# Pyr0-Piezo_Direct_Extruder_Board2_0_0.net
KiCad netlist of a schematic drawn in EAGLE
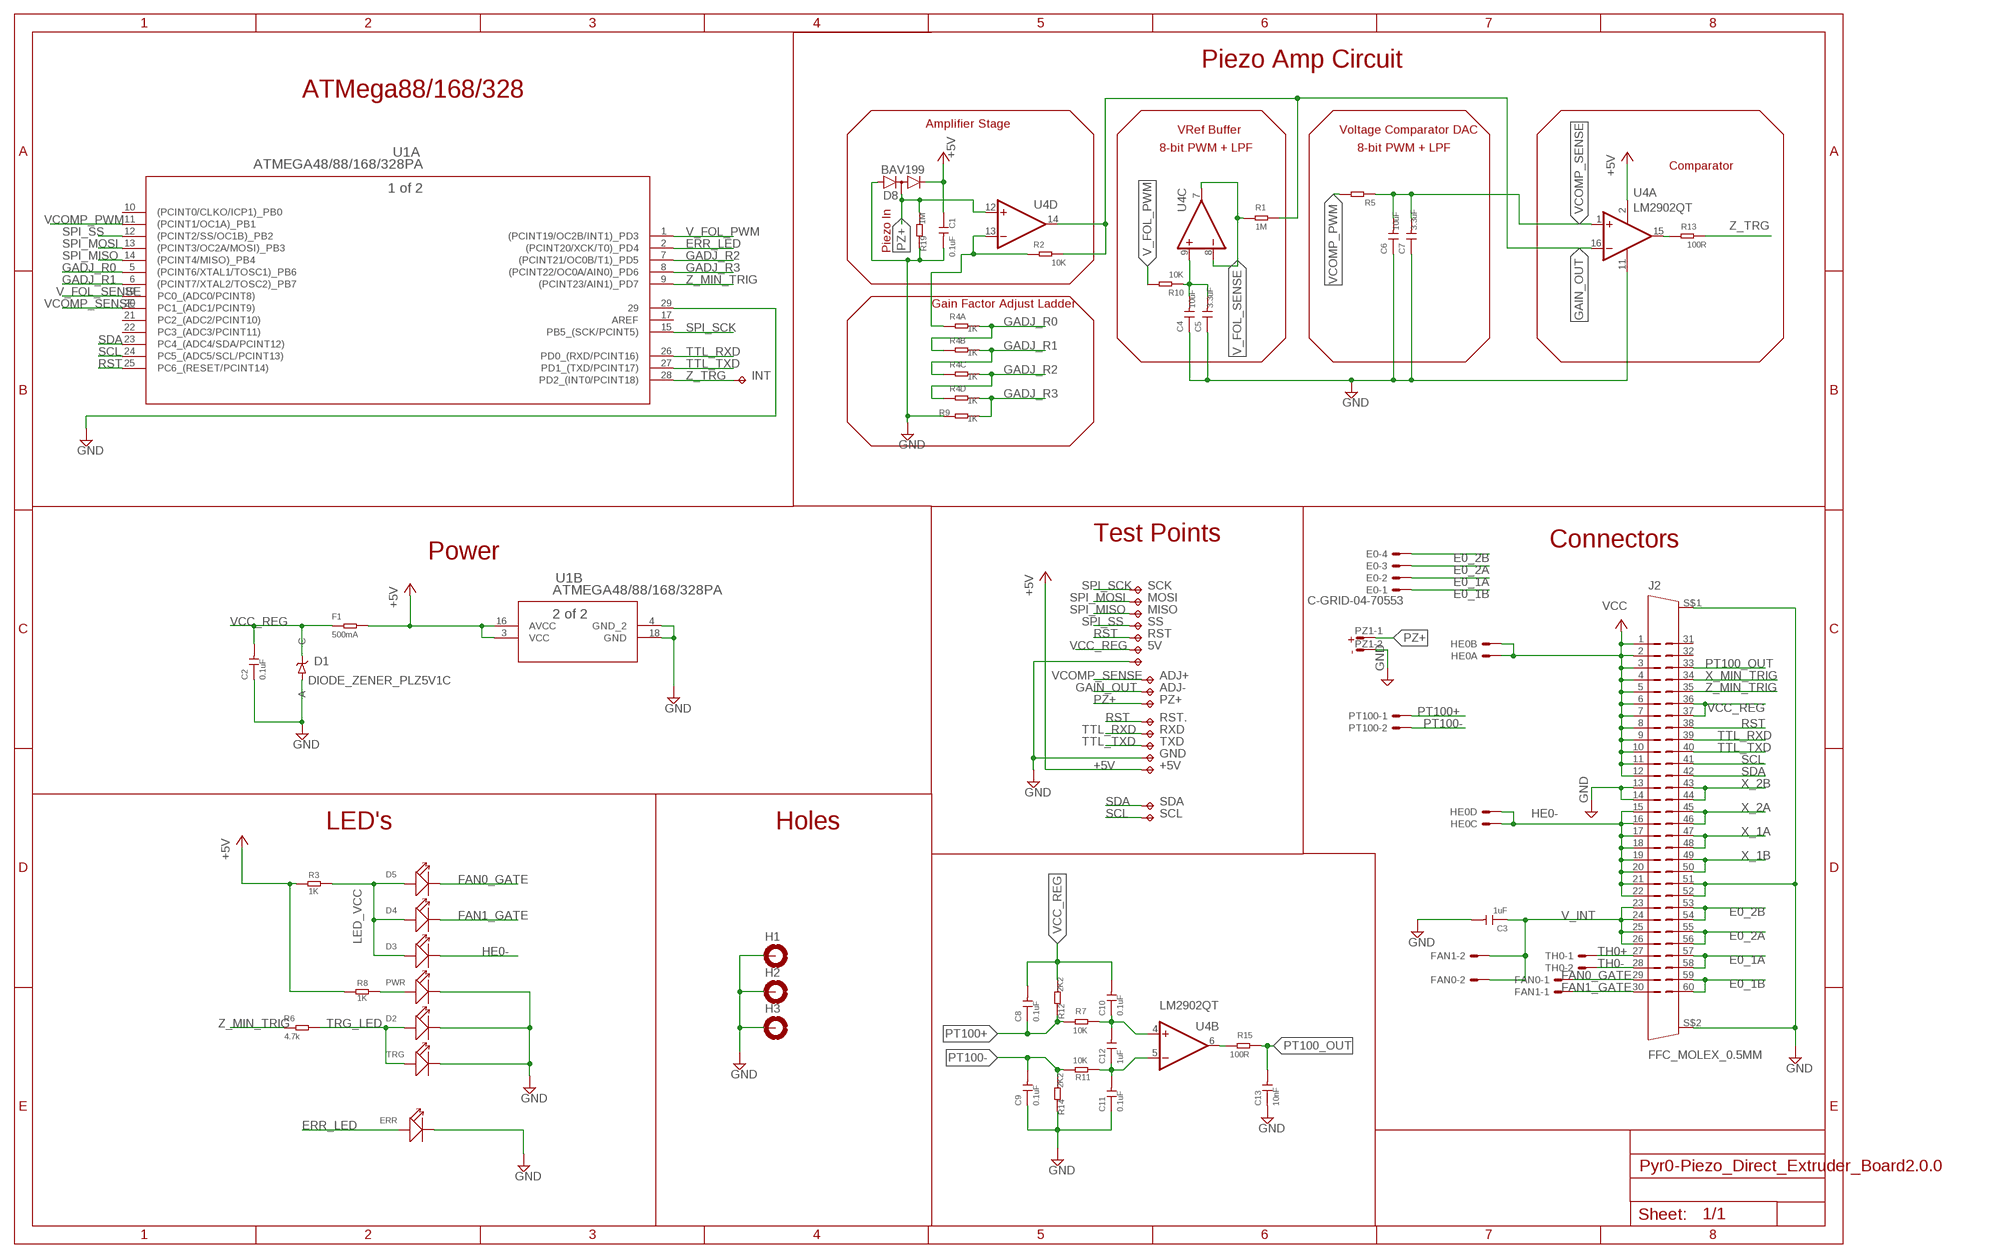
[diagram p0: schematic, sheet 1]

(export (version "E")
  (design (tool "Eeschema 10.0.6"))
  (components
    (comp (ref "+5V")
      (value "TPTP13SQ")
      (footprint "eagle-import:TP13SQ")
      (libsource (lib "eagle-import") (part "testpad_385_TPTP13SQ"))
    )
    (comp (ref "5V")
      (value "TPTP13SQ")
      (footprint "eagle-import:TP13SQ")
      (libsource (lib "eagle-import") (part "TPTP13SQ"))
    )
    (comp (ref "ADJ+")
      (value "TPTP13SQ")
      (footprint "eagle-import:TP13SQ")
      (libsource (lib "eagle-import") (part "TPTP13SQ"))
    )
    (comp (ref "ADJ-")
      (value "TPTP13SQ")
      (footprint "eagle-import:TP13SQ")
      (libsource (lib "eagle-import") (part "TPTP13SQ"))
    )
    (comp (ref "C1")
      (value "0.1uF")
      (footprint "eagle-import:CAPC1005X50")
      (libsource (lib "eagle-import") (part "CERAMIC-1NF-50V-10%-X7R(0402)CAP_0402"))
    )
    (comp (ref "C2")
      (value "0.1uF")
      (footprint "eagle-import:CAPC1005X50")
      (libsource (lib "eagle-import") (part "CERAMIC-1NF-50V-10%-X7R(0402)CAP_0402"))
    )
    (comp (ref "C3")
      (value "1uF")
      (footprint "eagle-import:CAPC1609X80")
      (libsource (lib "eagle-import") (part "SEEED-CAPACITOR_CERAMIC-10UF-25V-10%-X5R(0805)CAP_0603_GEN"))
    )
    (comp (ref "C4")
      (value "10uF")
      (footprint "eagle-import:CAPC1005X50")
      (libsource (lib "eagle-import") (part "CERAMIC-1NF-50V-10%-X7R(0402)CAP_0402"))
    )
    (comp (ref "C5")
      (value "3.3uF")
      (footprint "eagle-import:CAPC1609X80")
      (libsource (lib "eagle-import") (part "SEEED-CAPACITOR_CERAMIC-10UF-25V-10%-X5R(0805)CAP_0603_GEN"))
    )
    (comp (ref "C6")
      (value "10uF")
      (footprint "eagle-import:CAPC1005X50")
      (libsource (lib "eagle-import") (part "CERAMIC-1NF-50V-10%-X7R(0402)CAP_0402"))
    )
    (comp (ref "C7")
      (value "3.3uF")
      (footprint "eagle-import:CAPC1609X80")
      (libsource (lib "eagle-import") (part "SEEED-CAPACITOR_CERAMIC-10UF-25V-10%-X5R(0805)CAP_0603_GEN"))
    )
    (comp (ref "C8")
      (value "0.1uF")
      (footprint "eagle-import:CAPC1005X50")
      (libsource (lib "eagle-import") (part "CERAMIC-1NF-50V-10%-X7R(0402)CAP_0402"))
    )
    (comp (ref "C9")
      (value "0.1uF")
      (footprint "eagle-import:CAPC1005X50")
      (libsource (lib "eagle-import") (part "CERAMIC-1NF-50V-10%-X7R(0402)CAP_0402"))
    )
    (comp (ref "C10")
      (value "0.1uF")
      (footprint "eagle-import:CAPC1005X50")
      (libsource (lib "eagle-import") (part "CERAMIC-1NF-50V-10%-X7R(0402)CAP_0402"))
    )
    (comp (ref "C11")
      (value "0.1uF")
      (footprint "eagle-import:CAPC1005X50")
      (libsource (lib "eagle-import") (part "CERAMIC-1NF-50V-10%-X7R(0402)CAP_0402"))
    )
    (comp (ref "C12")
      (value "1uF")
      (footprint "eagle-import:CAPC1005X50")
      (libsource (lib "eagle-import") (part "CERAMIC-1NF-50V-10%-X7R(0402)CAP_0402"))
    )
    (comp (ref "C13")
      (value "10nF")
      (footprint "eagle-import:CAPC1005X50")
      (libsource (lib "eagle-import") (part "CERAMIC-1NF-50V-10%-X7R(0402)CAP_0402"))
    )
    (comp (ref "D1")
      (value "DIODE_ZENER_PLZ5V1C")
      (footprint "eagle-import:DO-219AC")
      (libsource (lib "eagle-import") (part "DIODE_ZENER_PLZ5V1C"))
    )
    (comp (ref "D2")
      (value "SEEED-LED_SMD-LED-CLEAR-BLUE(0603)LED_0603")
      (footprint "eagle-import:SEEED-LED_LED-0603")
      (libsource (lib "eagle-import") (part "SEEED-LED_SMD-LED-CLEAR-BLUE(0603)LED_0603"))
    )
    (comp (ref "D3")
      (value "SEEED-LED_SMD-LED-CLEAR-BLUE(0603)LED_0603")
      (footprint "eagle-import:SEEED-LED_LED-0603")
      (libsource (lib "eagle-import") (part "SEEED-LED_SMD-LED-CLEAR-BLUE(0603)LED_0603"))
    )
    (comp (ref "D4")
      (value "SEEED-LED_SMD-LED-CLEAR-BLUE(0603)LED_0603")
      (footprint "eagle-import:SEEED-LED_LED-0603")
      (libsource (lib "eagle-import") (part "SEEED-LED_SMD-LED-CLEAR-BLUE(0603)LED_0603"))
    )
    (comp (ref "D5")
      (value "SEEED-LED_SMD-LED-CLEAR-BLUE(0603)LED_0603")
      (footprint "eagle-import:SEEED-LED_LED-0603")
      (libsource (lib "eagle-import") (part "SEEED-LED_SMD-LED-CLEAR-BLUE(0603)LED_0603"))
    )
    (comp (ref "D8")
      (value "BAV199")
      (footprint "eagle-import:SOT23")
      (libsource (lib "eagle-import") (part "BAV199"))
    )
    (comp (ref "E0")
      (value "C-GRID-04-70553")
      (footprint "eagle-import:70553-04")
      (fields (field (name "MF") "MOLEX"))
      (libsource (lib "eagle-import") (part "C-GRID-04-70553"))
    )
    (comp (ref "ERR")
      (value "SEEED-LED_SMD-LED-CLEAR-BLUE(0603)LED_0603")
      (footprint "eagle-import:SEEED-LED_LED-0603")
      (libsource (lib "eagle-import") (part "SEEED-LED_SMD-LED-CLEAR-BLUE(0603)LED_0603"))
    )
    (comp (ref "F1")
      (value "500mA")
      (footprint "eagle-import:SEEED-RESISTOR_R0603")
      (libsource (lib "eagle-import") (part "SEEED-RESISTOR_SMD-RES-1.5K-1%-1/10W(0603)DETAILED_MODEL"))
    )
    (comp (ref "FAN0")
      (value "CON-MOLEX-2P-1.27MM048")
      (footprint "eagle-import:53048-02")
      (fields (field (name "MF") "MOLEX") (field (name "MPN") "53048-0210"))
      (libsource (lib "eagle-import") (part "CON-MOLEX-2P-1.27MM048"))
    )
    (comp (ref "FAN1")
      (value "CON-MOLEX-2P-1.27MM048")
      (footprint "eagle-import:53048-02")
      (fields (field (name "MF") "MOLEX") (field (name "MPN") "53048-0210"))
      (libsource (lib "eagle-import") (part "CON-MOLEX-2P-1.27MM048"))
    )
    (comp (ref "GND")
      (value "TPTP13SQ")
      (footprint "eagle-import:TP13SQ")
      (libsource (lib "eagle-import") (part "testpad_385_TPTP13SQ"))
    )
    (comp (ref "H1")
      (value "HOLES_MOUNT-PAD-ROUND3.2")
      (footprint "eagle-import:HOLES_3,2-PAD")
      (libsource (lib "eagle-import") (part "HOLES_MOUNT-PAD-ROUND3.2"))
    )
    (comp (ref "H2")
      (value "HOLES_MOUNT-PAD-ROUND3.2")
      (footprint "eagle-import:HOLES_3,2-PAD")
      (libsource (lib "eagle-import") (part "HOLES_MOUNT-PAD-ROUND3.2"))
    )
    (comp (ref "H3")
      (value "HOLES_MOUNT-PAD-ROUND3.2")
      (footprint "eagle-import:HOLES_3,2-PAD")
      (libsource (lib "eagle-import") (part "HOLES_MOUNT-PAD-ROUND3.2"))
    )
    (comp (ref "HE0")
      (value "JST-2.54-2X2JST-DUPONT-2.54-2X2")
      (footprint "eagle-import:HDRRAR4W64P254_2X2_556X736X556B")
      (libsource (lib "eagle-import") (part "JST-2.54-2X2JST-DUPONT-2.54-2X2"))
    )
    (comp (ref "INT")
      (value "TPTP06R")
      (footprint "eagle-import:TP06R")
      (libsource (lib "eagle-import") (part "testpad_385_TPTP06R"))
    )
    (comp (ref "J2")
      (value "FFC_MOLEX_0.5MM")
      (footprint "eagle-import:FFC-60P_0.5_MOLEX_505110-6091")
      (libsource (lib "eagle-import") (part "FFC_MOLEX_0.5MM"))
    )
    (comp (ref "MISO")
      (value "TPTP13SQ")
      (footprint "eagle-import:TP13SQ")
      (libsource (lib "eagle-import") (part "TPTP13SQ"))
    )
    (comp (ref "MOSI")
      (value "TPTP13SQ")
      (footprint "eagle-import:TP13SQ")
      (libsource (lib "eagle-import") (part "TPTP13SQ"))
    )
    (comp (ref "PT100")
      (value "CON-MOLEX-2P-1.27MM048")
      (footprint "eagle-import:53048-02")
      (fields (field (name "MF") "MOLEX") (field (name "MPN") "53048-0210"))
      (libsource (lib "eagle-import") (part "CON-MOLEX-2P-1.27MM048"))
    )
    (comp (ref "PWR")
      (value "SEEED-LED_SMD-LED-CLEAR-BLUE(0603)LED_0603")
      (footprint "eagle-import:SEEED-LED_LED-0603")
      (libsource (lib "eagle-import") (part "SEEED-LED_SMD-LED-CLEAR-BLUE(0603)LED_0603"))
    )
    (comp (ref "PZ+")
      (value "TPTP13SQ")
      (footprint "eagle-import:TP13SQ")
      (libsource (lib "eagle-import") (part "TPTP13SQ"))
    )
    (comp (ref "PZ1")
      (value "CON-MOLEX-2P-1.27MM048")
      (footprint "eagle-import:53048-02")
      (fields (field (name "MF") "MOLEX") (field (name "MPN") "53048-0210"))
      (libsource (lib "eagle-import") (part "CON-MOLEX-2P-1.27MM048"))
    )
    (comp (ref "R1")
      (value "1M")
      (footprint "eagle-import:R0402")
      (fields (field (name "MPN") "RC0402JR-070RL"))
      (libsource (lib "eagle-import") (part "SMD-RES-0R-5%-1/16W(0402)"))
    )
    (comp (ref "R2")
      (value "10K")
      (footprint "eagle-import:R0402")
      (fields (field (name "MPN") "RC0402JR-070RL"))
      (libsource (lib "eagle-import") (part "SMD-RES-0R-5%-1/16W(0402)"))
    )
    (comp (ref "R3")
      (value "1K")
      (footprint "eagle-import:R0402")
      (fields (field (name "MPN") "RC0402JR-070RL"))
      (libsource (lib "eagle-import") (part "SMD-RES-0R-5%-1/16W(0402)"))
    )
    (comp (ref "R4")
      (value "1K")
      (footprint "eagle-import:EXBN8V")
      (libsource (lib "eagle-import") (part "RESISTOR_NETWORK_X40804"))
    )
    (comp (ref "R5")
      (value "10K")
      (footprint "eagle-import:SEEED-RESISTOR_R0603")
      (libsource (lib "eagle-import") (part "SEEED-RESISTOR_SMD-RES-1.5K-1%-1/10W(0603)DETAILED_MODEL"))
    )
    (comp (ref "R6")
      (value "4.7k")
      (footprint "eagle-import:R0402")
      (fields (field (name "MPN") "RC0402JR-070RL"))
      (libsource (lib "eagle-import") (part "SMD-RES-0R-5%-1/16W(0402)"))
    )
    (comp (ref "R7")
      (value "10K")
      (footprint "eagle-import:R0402")
      (fields (field (name "MPN") "RC0402JR-070RL"))
      (libsource (lib "eagle-import") (part "SMD-RES-0R-5%-1/16W(0402)"))
    )
    (comp (ref "R8")
      (value "1K")
      (footprint "eagle-import:R0402")
      (fields (field (name "MPN") "RC0402JR-070RL"))
      (libsource (lib "eagle-import") (part "SMD-RES-0R-5%-1/16W(0402)"))
    )
    (comp (ref "R9")
      (value "1K")
      (footprint "eagle-import:R0402")
      (fields (field (name "MPN") "RC0402JR-070RL"))
      (libsource (lib "eagle-import") (part "SMD-RES-0R-5%-1/16W(0402)"))
    )
    (comp (ref "R10")
      (value "10K")
      (footprint "eagle-import:R0402")
      (fields (field (name "MPN") "RC0402JR-070RL"))
      (libsource (lib "eagle-import") (part "SMD-RES-0R-5%-1/16W(0402)"))
    )
    (comp (ref "R11")
      (value "10K")
      (footprint "eagle-import:R0402")
      (fields (field (name "MPN") "RC0402JR-070RL"))
      (libsource (lib "eagle-import") (part "SMD-RES-0R-5%-1/16W(0402)"))
    )
    (comp (ref "R12")
      (value "2K2")
      (footprint "eagle-import:R0402")
      (fields (field (name "MPN") "RC0402JR-070RL"))
      (libsource (lib "eagle-import") (part "SMD-RES-0R-5%-1/16W(0402)"))
    )
    (comp (ref "R13")
      (value "100R")
      (footprint "eagle-import:R0402")
      (fields (field (name "MPN") "RC0402JR-070RL"))
      (libsource (lib "eagle-import") (part "SMD-RES-0R-5%-1/16W(0402)"))
    )
    (comp (ref "R14")
      (value "2K2")
      (footprint "eagle-import:R0402")
      (fields (field (name "MPN") "RC0402JR-070RL"))
      (libsource (lib "eagle-import") (part "SMD-RES-0R-5%-1/16W(0402)"))
    )
    (comp (ref "R15")
      (value "100R")
      (footprint "eagle-import:R0402")
      (fields (field (name "MPN") "RC0402JR-070RL"))
      (libsource (lib "eagle-import") (part "SMD-RES-0R-5%-1/16W(0402)"))
    )
    (comp (ref "R19")
      (value "1M")
      (footprint "eagle-import:R0402")
      (fields (field (name "MPN") "RC0402JR-070RL"))
      (libsource (lib "eagle-import") (part "SMD-RES-0R-5%-1/16W(0402)"))
    )
    (comp (ref "RST")
      (value "TPTP13SQ")
      (footprint "eagle-import:TP13SQ")
      (libsource (lib "eagle-import") (part "TPTP13SQ"))
    )
    (comp (ref "RST.")
      (value "TPTP13SQ")
      (footprint "eagle-import:TP13SQ")
      (libsource (lib "eagle-import") (part "testpad_385_TPTP13SQ"))
    )
    (comp (ref "RXD")
      (value "TPTP13SQ")
      (footprint "eagle-import:TP13SQ")
      (libsource (lib "eagle-import") (part "testpad_385_TPTP13SQ"))
    )
    (comp (ref "SCK")
      (value "TPTP13SQ")
      (footprint "eagle-import:TP13SQ")
      (libsource (lib "eagle-import") (part "TPTP13SQ"))
    )
    (comp (ref "SCL")
      (value "TPTP13SQ")
      (footprint "eagle-import:TP13SQ")
      (libsource (lib "eagle-import") (part "testpad_385_TPTP13SQ"))
    )
    (comp (ref "SDA")
      (value "TPTP13SQ")
      (footprint "eagle-import:TP13SQ")
      (libsource (lib "eagle-import") (part "testpad_385_TPTP13SQ"))
    )
    (comp (ref "SS")
      (value "TPTP06R")
      (footprint "eagle-import:TP06R")
      (libsource (lib "eagle-import") (part "testpad_385_TPTP06R"))
    )
    (comp (ref "TH0")
      (value "CON-MOLEX-2P-1.27MM048")
      (footprint "eagle-import:53048-02")
      (fields (field (name "MF") "MOLEX") (field (name "MPN") "53048-0210"))
      (libsource (lib "eagle-import") (part "CON-MOLEX-2P-1.27MM048"))
    )
    (comp (ref "TRG")
      (value "SEEED-LED_SMD-LED-CLEAR-BLUE(0603)LED_0603")
      (footprint "eagle-import:SEEED-LED_LED-0603")
      (libsource (lib "eagle-import") (part "SEEED-LED_SMD-LED-CLEAR-BLUE(0603)LED_0603"))
    )
    (comp (ref "TXD")
      (value "TPTP13SQ")
      (footprint "eagle-import:TP13SQ")
      (libsource (lib "eagle-import") (part "testpad_385_TPTP13SQ"))
    )
    (comp (ref "U1")
      (value "ATMEGA48/88/168/328PA")
      (footprint "eagle-import:28M1")
      (fields (field (name "MANUFACTURER_PART_NUMBER") "ATMEGA48PAMMHR"))
      (libsource (lib "eagle-import") (part "ATMEGA48/88/168/328PA"))
    )
    (comp (ref "U4")
      (value "LM2902QT")
      (footprint "eagle-import:QFN16")
      (libsource (lib "eagle-import") (part "LM2902QT"))
    )
    (comp (ref "⏚")
      (value "TPTP13SQ")
      (footprint "eagle-import:TP13SQ")
      (libsource (lib "eagle-import") (part "testpad_385_TPTP13SQ"))
    )
  )
  (nets
    (net (code "1") (name "+5V") (class "Default")
      (node (ref "+5V") (pin "TP") (pinfunction "TP_TP") (pintype "input"))
      (node (ref "C1") (pin "1") (pinfunction "1_1") (pintype "passive"))
      (node (ref "D8") (pin "2") (pinfunction "C_2") (pintype "passive"))
      (node (ref "F1") (pin "2") (pinfunction "2_2") (pintype "passive"))
      (node (ref "R3") (pin "1") (pinfunction "1_1") (pintype "passive"))
      (node (ref "R8") (pin "1") (pinfunction "1_1") (pintype "passive"))
      (node (ref "U1") (pin "16") (pinfunction "AVCC_16") (pintype "power_in"))
      (node (ref "U1") (pin "3") (pinfunction "VCC_3") (pintype "power_in"))
      (node (ref "U4") (pin "2") (pinfunction "V+_2") (pintype "power_in"))
    )
    (net (code "2") (name "/E0_1A") (class "Default")
      (node (ref "E0") (pin "2") (pinfunction "S_2") (pintype "passive"))
      (node (ref "J2") (pin "57") (pinfunction "63_57") (pintype "passive"))
      (node (ref "J2") (pin "58") (pinfunction "64_58") (pintype "passive"))
    )
    (net (code "3") (name "/E0_1B") (class "Default")
      (node (ref "E0") (pin "1") (pinfunction "S_1") (pintype "passive"))
      (node (ref "J2") (pin "59") (pinfunction "65_59") (pintype "passive"))
      (node (ref "J2") (pin "60") (pinfunction "66_60") (pintype "passive"))
    )
    (net (code "4") (name "/E0_2A") (class "Default")
      (node (ref "E0") (pin "3") (pinfunction "S_3") (pintype "passive"))
      (node (ref "J2") (pin "55") (pinfunction "61_55") (pintype "passive"))
      (node (ref "J2") (pin "56") (pinfunction "62_56") (pintype "passive"))
    )
    (net (code "5") (name "/E0_2B") (class "Default")
      (node (ref "E0") (pin "4") (pinfunction "S_4") (pintype "passive"))
      (node (ref "J2") (pin "53") (pinfunction "59_53") (pintype "passive"))
      (node (ref "J2") (pin "54") (pinfunction "60_54") (pintype "passive"))
    )
    (net (code "6") (name "/ERR_LED") (class "Default")
      (node (ref "ERR") (pin "+") (pinfunction "+_+") (pintype "passive"))
      (node (ref "U1") (pin "2") (pinfunction "(PCINT20/XCK/T0)_PD4_2") (pintype "bidirectional"))
    )
    (net (code "7") (name "/FAN0_GATE") (class "Default")
      (node (ref "D5") (pin "-") (pinfunction "-_-") (pintype "passive"))
      (node (ref "FAN0") (pin "1") (pinfunction "S_1") (pintype "passive"))
      (node (ref "J2") (pin "29") (pinfunction "31_29") (pintype "passive"))
    )
    (net (code "8") (name "/FAN1_GATE") (class "Default")
      (node (ref "D4") (pin "-") (pinfunction "-_-") (pintype "passive"))
      (node (ref "FAN1") (pin "1") (pinfunction "S_1") (pintype "passive"))
      (node (ref "J2") (pin "30") (pinfunction "32_30") (pintype "passive"))
    )
    (net (code "9") (name "/GADJ_R0") (class "Default")
      (node (ref "R4") (pin "2") (pinfunction "1_2") (pintype "passive"))
      (node (ref "R4") (pin "8") (pinfunction "2_8") (pintype "passive"))
      (node (ref "U1") (pin "5") (pinfunction "(PCINT6/XTAL1/TOSC1)_PB6_5") (pintype "bidirectional"))
    )
    (net (code "10") (name "/GADJ_R1") (class "Default")
      (node (ref "R4") (pin "3") (pinfunction "1_3") (pintype "passive"))
      (node (ref "R4") (pin "7") (pinfunction "2_7") (pintype "passive"))
      (node (ref "U1") (pin "6") (pinfunction "(PCINT7/XTAL2/TOSC2)_PB7_6") (pintype "bidirectional"))
    )
    (net (code "11") (name "/GADJ_R2") (class "Default")
      (node (ref "R4") (pin "4") (pinfunction "1_4") (pintype "passive"))
      (node (ref "R4") (pin "6") (pinfunction "2_6") (pintype "passive"))
      (node (ref "U1") (pin "7") (pinfunction "(PCINT21/OC0B/T1)_PD5_7") (pintype "bidirectional"))
    )
    (net (code "12") (name "/GADJ_R3") (class "Default")
      (node (ref "R4") (pin "5") (pinfunction "2_5") (pintype "passive"))
      (node (ref "R9") (pin "2") (pinfunction "2_2") (pintype "passive"))
      (node (ref "U1") (pin "8") (pinfunction "(PCINT22/OC0A/AIN0)_PD6_8") (pintype "bidirectional"))
    )
    (net (code "13") (name "/HE0-") (class "Default")
      (node (ref "D3") (pin "-") (pinfunction "-_-") (pintype "passive"))
      (node (ref "HE0") (pin "3") (pinfunction "S_3") (pintype "passive"))
      (node (ref "HE0") (pin "4") (pinfunction "S_4") (pintype "passive"))
      (node (ref "J2") (pin "15") (pinfunction "17_15") (pintype "passive"))
      (node (ref "J2") (pin "16") (pinfunction "18_16") (pintype "passive"))
      (node (ref "J2") (pin "17") (pinfunction "19_17") (pintype "passive"))
      (node (ref "J2") (pin "18") (pinfunction "20_18") (pintype "passive"))
      (node (ref "J2") (pin "19") (pinfunction "21_19") (pintype "passive"))
      (node (ref "J2") (pin "20") (pinfunction "22_20") (pintype "passive"))
      (node (ref "J2") (pin "21") (pinfunction "23_21") (pintype "passive"))
      (node (ref "J2") (pin "22") (pinfunction "24_22") (pintype "passive"))
    )
    (net (code "14") (name "/LED_VCC") (class "Default")
      (node (ref "D3") (pin "+") (pinfunction "+_+") (pintype "passive"))
      (node (ref "D4") (pin "+") (pinfunction "+_+") (pintype "passive"))
      (node (ref "D5") (pin "+") (pinfunction "+_+") (pintype "passive"))
      (node (ref "R3") (pin "2") (pinfunction "2_2") (pintype "passive"))
    )
    (net (code "15") (name "/RST") (class "Default")
      (node (ref "J2") (pin "38") (pinfunction "44_38") (pintype "passive"))
      (node (ref "RST") (pin "TP") (pinfunction "TP_TP") (pintype "input"))
      (node (ref "RST.") (pin "TP") (pinfunction "TP_TP") (pintype "input"))
      (node (ref "U1") (pin "25") (pinfunction "PC6_(RESET/PCINT14)_25") (pintype "bidirectional"))
    )
    (net (code "16") (name "/SCL") (class "Default")
      (node (ref "J2") (pin "41") (pinfunction "47_41") (pintype "passive"))
      (node (ref "SCL") (pin "TP") (pinfunction "TP_TP") (pintype "input"))
      (node (ref "U1") (pin "24") (pinfunction "PC5_(ADC5/SCL/PCINT13)_24") (pintype "bidirectional"))
    )
    (net (code "17") (name "/SDA") (class "Default")
      (node (ref "J2") (pin "42") (pinfunction "48_42") (pintype "passive"))
      (node (ref "SDA") (pin "TP") (pinfunction "TP_TP") (pintype "input"))
      (node (ref "U1") (pin "23") (pinfunction "PC4_(ADC4/SDA/PCINT12)_23") (pintype "bidirectional"))
    )
    (net (code "18") (name "/SPI_MISO") (class "Default")
      (node (ref "MISO") (pin "TP") (pinfunction "TP_TP") (pintype "input"))
      (node (ref "U1") (pin "14") (pinfunction "(PCINT4/MISO)_PB4_14") (pintype "bidirectional"))
    )
    (net (code "19") (name "/SPI_MOSI") (class "Default")
      (node (ref "MOSI") (pin "TP") (pinfunction "TP_TP") (pintype "input"))
      (node (ref "U1") (pin "13") (pinfunction "(PCINT3/OC2A/MOSI)_PB3_13") (pintype "bidirectional"))
    )
    (net (code "20") (name "/SPI_SCK") (class "Default")
      (node (ref "SCK") (pin "TP") (pinfunction "TP_TP") (pintype "input"))
      (node (ref "U1") (pin "15") (pinfunction "PB5_(SCK/PCINT5)_15") (pintype "bidirectional"))
    )
    (net (code "21") (name "/SPI_SS") (class "Default")
      (node (ref "SS") (pin "TP") (pinfunction "TP_TP") (pintype "input"))
      (node (ref "U1") (pin "12") (pinfunction "(PCINT2/SS/OC1B)_PB2_12") (pintype "bidirectional"))
    )
    (net (code "22") (name "/TH0+") (class "Default")
      (node (ref "J2") (pin "27") (pinfunction "29_27") (pintype "passive"))
      (node (ref "TH0") (pin "1") (pinfunction "S_1") (pintype "passive"))
    )
    (net (code "23") (name "/TH0-") (class "Default")
      (node (ref "J2") (pin "28") (pinfunction "30_28") (pintype "passive"))
      (node (ref "TH0") (pin "2") (pinfunction "S_2") (pintype "passive"))
    )
    (net (code "24") (name "/TRG_LED") (class "Default")
      (node (ref "D2") (pin "+") (pinfunction "+_+") (pintype "passive"))
      (node (ref "R6") (pin "2") (pinfunction "2_2") (pintype "passive"))
      (node (ref "TRG") (pin "+") (pinfunction "+_+") (pintype "passive"))
    )
    (net (code "25") (name "/TTL_RXD") (class "Default")
      (node (ref "J2") (pin "39") (pinfunction "45_39") (pintype "passive"))
      (node (ref "RXD") (pin "TP") (pinfunction "TP_TP") (pintype "input"))
      (node (ref "U1") (pin "26") (pinfunction "PD0_(RXD/PCINT16)_26") (pintype "bidirectional"))
    )
    (net (code "26") (name "/TTL_TXD") (class "Default")
      (node (ref "J2") (pin "40") (pinfunction "46_40") (pintype "passive"))
      (node (ref "TXD") (pin "TP") (pinfunction "TP_TP") (pintype "input"))
      (node (ref "U1") (pin "27") (pinfunction "PD1_(TXD/PCINT17)_27") (pintype "bidirectional"))
    )
    (net (code "27") (name "/V_INT") (class "Default")
      (node (ref "C3") (pin "1") (pinfunction "1_1") (pintype "passive"))
      (node (ref "FAN0") (pin "2") (pinfunction "S_2") (pintype "passive"))
      (node (ref "FAN1") (pin "2") (pinfunction "S_2") (pintype "passive"))
      (node (ref "J2") (pin "23") (pinfunction "25_23") (pintype "passive"))
      (node (ref "J2") (pin "24") (pinfunction "26_24") (pintype "passive"))
      (node (ref "J2") (pin "25") (pinfunction "27_25") (pintype "passive"))
      (node (ref "J2") (pin "26") (pinfunction "28_26") (pintype "passive"))
    )
    (net (code "28") (name "/X_1A") (class "Default")
      (node (ref "J2") (pin "47") (pinfunction "53_47") (pintype "passive"))
      (node (ref "J2") (pin "48") (pinfunction "54_48") (pintype "passive"))
    )
    (net (code "29") (name "/X_1B") (class "Default")
      (node (ref "J2") (pin "49") (pinfunction "55_49") (pintype "passive"))
      (node (ref "J2") (pin "50") (pinfunction "56_50") (pintype "passive"))
    )
    (net (code "30") (name "/X_2A") (class "Default")
      (node (ref "J2") (pin "45") (pinfunction "51_45") (pintype "passive"))
      (node (ref "J2") (pin "46") (pinfunction "52_46") (pintype "passive"))
    )
    (net (code "31") (name "/X_2B") (class "Default")
      (node (ref "J2") (pin "43") (pinfunction "49_43") (pintype "passive"))
      (node (ref "J2") (pin "44") (pinfunction "50_44") (pintype "passive"))
    )
    (net (code "32") (name "/X_MIN_TRIG") (class "Default")
      (node (ref "J2") (pin "34") (pinfunction "40_34") (pintype "passive"))
    )
    (net (code "33") (name "/Z_MIN_TRIG") (class "Default")
      (node (ref "J2") (pin "35") (pinfunction "41_35") (pintype "passive"))
      (node (ref "R6") (pin "1") (pinfunction "1_1") (pintype "passive"))
      (node (ref "U1") (pin "9") (pinfunction "(PCINT23/AIN1)_PD7_9") (pintype "bidirectional"))
    )
    (net (code "34") (name "/Z_TRG") (class "Default")
      (node (ref "INT") (pin "TP") (pinfunction "TP_TP") (pintype "input"))
      (node (ref "R13") (pin "2") (pinfunction "2_2") (pintype "passive"))
      (node (ref "U1") (pin "28") (pinfunction "PD2_(INT0/PCINT18)_28") (pintype "bidirectional"))
    )
    (net (code "35") (name "GAIN_OUT") (class "Default")
      (node (ref "ADJ-") (pin "TP") (pinfunction "TP_TP") (pintype "input"))
      (node (ref "R1") (pin "2") (pinfunction "2_2") (pintype "passive"))
      (node (ref "R2") (pin "2") (pinfunction "2_2") (pintype "passive"))
      (node (ref "U4") (pin "14") (pinfunction "OUT_14") (pintype "output"))
      (node (ref "U4") (pin "16") (pinfunction "-IN_16") (pintype "input"))
    )
    (net (code "36") (name "GND") (class "Default")
      (node (ref "C1") (pin "2") (pinfunction "2_2") (pintype "passive"))
      (node (ref "C11") (pin "1") (pinfunction "1_1") (pintype "passive"))
      (node (ref "C13") (pin "1") (pinfunction "1_1") (pintype "passive"))
      (node (ref "C2") (pin "1") (pinfunction "1_1") (pintype "passive"))
      (node (ref "C3") (pin "2") (pinfunction "2_2") (pintype "passive"))
      (node (ref "C4") (pin "1") (pinfunction "1_1") (pintype "passive"))
      (node (ref "C5") (pin "1") (pinfunction "1_1") (pintype "passive"))
      (node (ref "C6") (pin "1") (pinfunction "1_1") (pintype "passive"))
      (node (ref "C7") (pin "1") (pinfunction "1_1") (pintype "passive"))
      (node (ref "C9") (pin "1") (pinfunction "1_1") (pintype "passive"))
      (node (ref "D1") (pin "P$1") (pinfunction "A_P$1") (pintype "passive"))
      (node (ref "D2") (pin "-") (pinfunction "-_-") (pintype "passive"))
      (node (ref "D8") (pin "1") (pinfunction "A_1") (pintype "passive"))
      (node (ref "ERR") (pin "-") (pinfunction "-_-") (pintype "passive"))
      (node (ref "GND") (pin "TP") (pinfunction "TP_TP") (pintype "input"))
      (node (ref "H1") (pin "B3,2") (pinfunction "MOUNT_B3,2") (pintype "passive"))
      (node (ref "H2") (pin "B3,2") (pinfunction "MOUNT_B3,2") (pintype "passive"))
      (node (ref "H3") (pin "B3,2") (pinfunction "MOUNT_B3,2") (pintype "passive"))
      (node (ref "J2") (pin "13") (pinfunction "15_13") (pintype "passive"))
      (node (ref "J2") (pin "14") (pinfunction "16_14") (pintype "passive"))
      (node (ref "J2") (pin "51") (pinfunction "57_51") (pintype "passive"))
      (node (ref "J2") (pin "52") (pinfunction "58_52") (pintype "passive"))
      (node (ref "J2") (pin "S$1") (pinfunction "S_S$1") (pintype "passive"))
      (node (ref "J2") (pin "S$2") (pinfunction "S_S$2") (pintype "passive"))
      (node (ref "PWR") (pin "-") (pinfunction "-_-") (pintype "passive"))
      (node (ref "PZ1") (pin "2") (pinfunction "S_2") (pintype "passive"))
      (node (ref "R14") (pin "1") (pinfunction "1_1") (pintype "passive"))
      (node (ref "R19") (pin "1") (pinfunction "1_1") (pintype "passive"))
      (node (ref "R9") (pin "1") (pinfunction "1_1") (pintype "passive"))
      (node (ref "TRG") (pin "-") (pinfunction "-_-") (pintype "passive"))
      (node (ref "U1") (pin "18") (pinfunction "GND_18") (pintype "power_in"))
      (node (ref "U1") (pin "29") (pinfunction "29_29") (pintype "passive"))
      (node (ref "U1") (pin "4") (pinfunction "GND_2_4") (pintype "power_in"))
      (node (ref "U4") (pin "11") (pinfunction "V-_11") (pintype "power_in"))
      (node (ref "⏚") (pin "TP") (pinfunction "TP_TP") (pintype "input"))
    )
    (net (code "37") (name "Net-(PWR-Pad+)") (class "Default")
      (node (ref "PWR") (pin "+") (pinfunction "+_+") (pintype "passive"))
      (node (ref "R8") (pin "2") (pinfunction "2_2") (pintype "passive"))
    )
    (net (code "38") (name "Net-(U4A-OUT)") (class "Default")
      (node (ref "R13") (pin "1") (pinfunction "1_1") (pintype "passive"))
      (node (ref "U4") (pin "15") (pinfunction "OUT_15") (pintype "output"))
    )
    (net (code "39") (name "Net-(U4B-+IN)") (class "Default")
      (node (ref "C10") (pin "1") (pinfunction "1_1") (pintype "passive"))
      (node (ref "C12") (pin "2") (pinfunction "2_2") (pintype "passive"))
      (node (ref "R7") (pin "1") (pinfunction "1_1") (pintype "passive"))
      (node (ref "U4") (pin "4") (pinfunction "+IN_4") (pintype "input"))
    )
    (net (code "40") (name "Net-(U4B--IN)") (class "Default")
      (node (ref "C11") (pin "2") (pinfunction "2_2") (pintype "passive"))
      (node (ref "C12") (pin "1") (pinfunction "1_1") (pintype "passive"))
      (node (ref "R11") (pin "1") (pinfunction "1_1") (pintype "passive"))
      (node (ref "U4") (pin "5") (pinfunction "-IN_5") (pintype "input"))
    )
    (net (code "41") (name "Net-(U4B-OUT)") (class "Default")
      (node (ref "R15") (pin "2") (pinfunction "2_2") (pintype "passive"))
      (node (ref "U4") (pin "6") (pinfunction "OUT_6") (pintype "output"))
    )
    (net (code "42") (name "Net-(U4C-+IN)") (class "Default")
      (node (ref "C4") (pin "2") (pinfunction "2_2") (pintype "passive"))
      (node (ref "C5") (pin "2") (pinfunction "2_2") (pintype "passive"))
      (node (ref "R10") (pin "1") (pinfunction "1_1") (pintype "passive"))
      (node (ref "U4") (pin "9") (pinfunction "+IN_9") (pintype "input"))
    )
    (net (code "43") (name "Net-(U4D--IN)") (class "Default")
      (node (ref "R2") (pin "1") (pinfunction "1_1") (pintype "passive"))
      (node (ref "R4") (pin "1") (pinfunction "1_1") (pintype "passive"))
      (node (ref "U4") (pin "13") (pinfunction "-IN_13") (pintype "input"))
    )
    (net (code "44") (name "PT100+") (class "Default")
      (node (ref "C8") (pin "1") (pinfunction "1_1") (pintype "passive"))
      (node (ref "PT100") (pin "1") (pinfunction "S_1") (pintype "passive"))
      (node (ref "R12") (pin "1") (pinfunction "1_1") (pintype "passive"))
      (node (ref "R7") (pin "2") (pinfunction "2_2") (pintype "passive"))
    )
    (net (code "45") (name "PT100-") (class "Default")
      (node (ref "C9") (pin "2") (pinfunction "2_2") (pintype "passive"))
      (node (ref "PT100") (pin "2") (pinfunction "S_2") (pintype "passive"))
      (node (ref "R11") (pin "2") (pinfunction "2_2") (pintype "passive"))
      (node (ref "R14") (pin "2") (pinfunction "2_2") (pintype "passive"))
    )
    (net (code "46") (name "PT100_OUT") (class "Default")
      (node (ref "C13") (pin "2") (pinfunction "2_2") (pintype "passive"))
      (node (ref "J2") (pin "33") (pinfunction "39_33") (pintype "passive"))
      (node (ref "R15") (pin "1") (pinfunction "1_1") (pintype "passive"))
    )
    (net (code "47") (name "PZ+") (class "Default")
      (node (ref "D8") (pin "3") (pinfunction "AC_3") (pintype "passive"))
      (node (ref "PZ+") (pin "TP") (pinfunction "TP_TP") (pintype "input"))
      (node (ref "PZ1") (pin "1") (pinfunction "S_1") (pintype "passive"))
      (node (ref "R19") (pin "2") (pinfunction "2_2") (pintype "passive"))
      (node (ref "U4") (pin "12") (pinfunction "+IN_12") (pintype "input"))
    )
    (net (code "48") (name "VCC") (class "Default")
      (node (ref "HE0") (pin "1") (pinfunction "S_1") (pintype "passive"))
      (node (ref "HE0") (pin "2") (pinfunction "S_2") (pintype "passive"))
      (node (ref "J2") (pin "1") (pinfunction "3_1") (pintype "passive"))
      (node (ref "J2") (pin "10") (pinfunction "12_10") (pintype "passive"))
      (node (ref "J2") (pin "11") (pinfunction "13_11") (pintype "passive"))
      (node (ref "J2") (pin "12") (pinfunction "14_12") (pintype "passive"))
      (node (ref "J2") (pin "2") (pinfunction "4_2") (pintype "passive"))
      (node (ref "J2") (pin "3") (pinfunction "5_3") (pintype "passive"))
      (node (ref "J2") (pin "4") (pinfunction "6_4") (pintype "passive"))
      (node (ref "J2") (pin "5") (pinfunction "7_5") (pintype "passive"))
      (node (ref "J2") (pin "6") (pinfunction "8_6") (pintype "passive"))
      (node (ref "J2") (pin "7") (pinfunction "9_7") (pintype "passive"))
      (node (ref "J2") (pin "8") (pinfunction "10_8") (pintype "passive"))
      (node (ref "J2") (pin "9") (pinfunction "11_9") (pintype "passive"))
    )
    (net (code "49") (name "VCC_REG") (class "Default")
      (node (ref "5V") (pin "TP") (pinfunction "TP_TP") (pintype "input"))
      (node (ref "C10") (pin "2") (pinfunction "2_2") (pintype "passive"))
      (node (ref "C2") (pin "2") (pinfunction "2_2") (pintype "passive"))
      (node (ref "C8") (pin "2") (pinfunction "2_2") (pintype "passive"))
      (node (ref "D1") (pin "P$2") (pinfunction "C_P$2") (pintype "passive"))
      (node (ref "F1") (pin "1") (pinfunction "1_1") (pintype "passive"))
      (node (ref "J2") (pin "36") (pinfunction "42_36") (pintype "passive"))
      (node (ref "J2") (pin "37") (pinfunction "43_37") (pintype "passive"))
      (node (ref "R12") (pin "2") (pinfunction "2_2") (pintype "passive"))
    )
    (net (code "50") (name "VCOMP_PWM") (class "Default")
      (node (ref "R5") (pin "2") (pinfunction "2_2") (pintype "passive"))
      (node (ref "U1") (pin "11") (pinfunction "(PCINT1/OC1A)_PB1_11") (pintype "bidirectional"))
    )
    (net (code "51") (name "VCOMP_SENSE") (class "Default")
      (node (ref "ADJ+") (pin "TP") (pinfunction "TP_TP") (pintype "input"))
      (node (ref "C6") (pin "2") (pinfunction "2_2") (pintype "passive"))
      (node (ref "C7") (pin "2") (pinfunction "2_2") (pintype "passive"))
      (node (ref "R5") (pin "1") (pinfunction "1_1") (pintype "passive"))
      (node (ref "U1") (pin "20") (pinfunction "PC1_(ADC1/PCINT9)_20") (pintype "bidirectional"))
      (node (ref "U4") (pin "1") (pinfunction "+IN_1") (pintype "input"))
    )
    (net (code "52") (name "V_FOL_PWM") (class "Default")
      (node (ref "R10") (pin "2") (pinfunction "2_2") (pintype "passive"))
      (node (ref "U1") (pin "1") (pinfunction "(PCINT19/OC2B/INT1)_PD3_1") (pintype "bidirectional"))
    )
    (net (code "53") (name "V_FOL_SENSE") (class "Default")
      (node (ref "R1") (pin "1") (pinfunction "1_1") (pintype "passive"))
      (node (ref "U1") (pin "19") (pinfunction "PC0_(ADC0/PCINT8)_19") (pintype "bidirectional"))
      (node (ref "U4") (pin "7") (pinfunction "OUT_7") (pintype "output"))
      (node (ref "U4") (pin "8") (pinfunction "-IN_8") (pintype "input"))
    )
    (net (code "54") (name "unconnected-(J2-37-Pad31)") (class "Default")
      (node (ref "J2") (pin "31") (pinfunction "37_31") (pintype "passive"))
    )
    (net (code "55") (name "unconnected-(J2-38-Pad32)") (class "Default")
      (node (ref "J2") (pin "32") (pinfunction "38_32") (pintype "passive"))
    )
    (net (code "56") (name "unconnected-(U1A-(PCINT0{slash}CLKO{slash}ICP1)_PB0-Pad10)") (class "Default")
      (node (ref "U1") (pin "10") (pinfunction "(PCINT0/CLKO/ICP1)_PB0_10") (pintype "bidirectional"))
    )
    (net (code "57") (name "unconnected-(U1A-AREF-Pad17)") (class "Default")
      (node (ref "U1") (pin "17") (pinfunction "AREF_17") (pintype "passive"))
    )
    (net (code "58") (name "unconnected-(U1A-PC2_(ADC2{slash}PCINT10)-Pad21)") (class "Default")
      (node (ref "U1") (pin "21") (pinfunction "PC2_(ADC2/PCINT10)_21") (pintype "bidirectional"))
    )
    (net (code "59") (name "unconnected-(U1A-PC3_(ADC3{slash}PCINT11)-Pad22)") (class "Default")
      (node (ref "U1") (pin "22") (pinfunction "PC3_(ADC3/PCINT11)_22") (pintype "bidirectional"))
    )
  )
)
